# TP1.net
KiCad netlist of a schematic drawn in Altium Designer
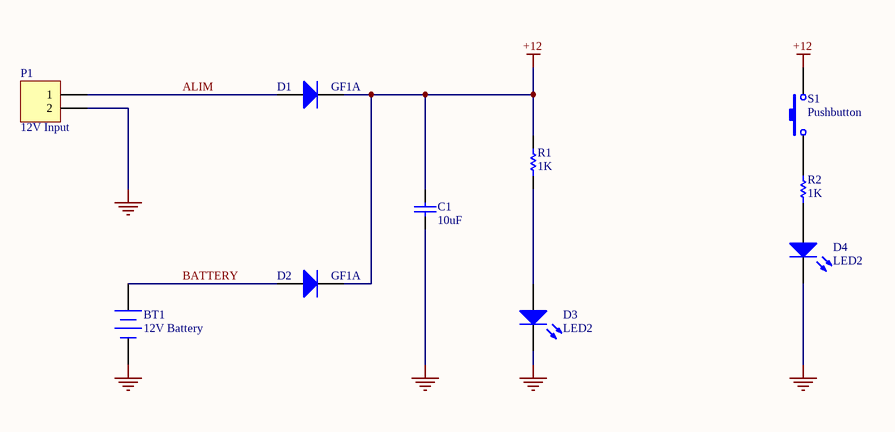
[diagram p0: TP1.SchDoc]

(export (version "E")
  (design (tool "Eeschema 10.0.6"))
  (components
    (comp (ref "BT1")
      (value "12V Battery")
      (footprint "BAT-2")
      (description "Multicell Battery")
      (fields (field (name "PUBLISHER") "Altium Limited"))
      (libsource (lib "Miscellaneous Devices") (part "Battery"))
    )
    (comp (ref "C1")
      (value "10uF")
      (footprint "RAD-0.3")
      (description "Capacitor")
      (fields (field (name "PUBLISHER") "Altium Limited"))
      (libsource (lib "Miscellaneous Devices") (part "Cap"))
    )
    (comp (ref "D1")
      (value "GF1A")
      (footprint "SMC")
      (description "Default Diode")
      (fields (field (name "PUBLISHER") "Altium Limited"))
      (libsource (lib "Miscellaneous Devices") (part "Diode"))
    )
    (comp (ref "D2")
      (value "GF1A")
      (footprint "SMC")
      (description "Default Diode")
      (fields (field (name "PUBLISHER") "Altium Limited"))
      (libsource (lib "Miscellaneous Devices") (part "Diode"))
    )
    (comp (ref "D3")
      (value "LED2")
      (footprint "LED-0")
      (description "Typical INFRARED GaAs LED")
      (fields (field (name "PUBLISHER") "Altium Limited"))
      (libsource (lib "Miscellaneous Devices") (part "LED0"))
    )
    (comp (ref "D4")
      (value "LED2")
      (footprint "LED-0")
      (description "Typical INFRARED GaAs LED")
      (fields (field (name "PUBLISHER") "Altium Limited"))
      (libsource (lib "Miscellaneous Devices") (part "LED0"))
    )
    (comp (ref "P1")
      (value "12V Input")
      (footprint "HDR1X2")
      (description "Header, 2-Pin")
      (fields (field (name "PUBLISHER") "Altium Limited"))
      (libsource (lib "Miscellaneous Connectors") (part "Header 2"))
    )
    (comp (ref "R1")
      (value "1K")
      (footprint "AXIAL-0.3")
      (description "Resistor")
      (fields (field (name "PUBLISHER") "Altium Limited"))
      (libsource (lib "Miscellaneous Devices") (part "Res1"))
    )
    (comp (ref "R2")
      (value "1K")
      (footprint "AXIAL-0.3")
      (description "Resistor")
      (fields (field (name "PUBLISHER") "Altium Limited"))
      (libsource (lib "Miscellaneous Devices") (part "Res1"))
    )
    (comp (ref "S1")
      (value "Pushbutton")
      (footprint "SPST-2")
      (description "Switch")
      (fields (field (name "PUBLISHER") "Altium Limited"))
      (libsource (lib "Miscellaneous Devices") (part "SW-PB"))
    )
  )
  (nets
    (net (code "1") (name "+12") (class "Default")
      (node (ref "C1") (pin "1") (pinfunction "1_1") (pintype "passive"))
      (node (ref "D1") (pin "2") (pinfunction "K_2") (pintype "passive"))
      (node (ref "D2") (pin "2") (pinfunction "K_2") (pintype "passive"))
      (node (ref "R1") (pin "2") (pinfunction "2_2") (pintype "passive"))
      (node (ref "S1") (pin "2") (pinfunction "2_2") (pintype "passive"))
    )
    (net (code "2") (name "/ALIM") (class "Default")
      (node (ref "D1") (pin "1") (pinfunction "A_1") (pintype "passive"))
      (node (ref "P1") (pin "1") (pinfunction "1_1") (pintype "passive"))
    )
    (net (code "3") (name "/BATTERY") (class "Default")
      (node (ref "BT1") (pin "1") (pinfunction "+_1") (pintype "passive"))
      (node (ref "D2") (pin "1") (pinfunction "A_1") (pintype "passive"))
    )
    (net (code "4") (name "GND") (class "Default")
      (node (ref "BT1") (pin "2") (pinfunction "-_2") (pintype "passive"))
      (node (ref "C1") (pin "2") (pinfunction "2_2") (pintype "passive"))
      (node (ref "D3") (pin "2") (pinfunction "K_2") (pintype "passive"))
      (node (ref "D4") (pin "2") (pinfunction "K_2") (pintype "passive"))
      (node (ref "P1") (pin "2") (pinfunction "2_2") (pintype "passive"))
    )
    (net (code "5") (name "Net-(D3-A)") (class "Default")
      (node (ref "D3") (pin "1") (pinfunction "A_1") (pintype "passive"))
      (node (ref "R1") (pin "1") (pinfunction "1_1") (pintype "passive"))
    )
    (net (code "6") (name "Net-(D4-A)") (class "Default")
      (node (ref "D4") (pin "1") (pinfunction "A_1") (pintype "passive"))
      (node (ref "R2") (pin "1") (pinfunction "1_1") (pintype "passive"))
    )
    (net (code "7") (name "Net-(R2-Pad2)") (class "Default")
      (node (ref "R2") (pin "2") (pinfunction "2_2") (pintype "passive"))
      (node (ref "S1") (pin "1") (pinfunction "1_1") (pintype "passive"))
    )
  )
)
